# AUDIO2.net
KiCad netlist of a schematic drawn in Altium Designer
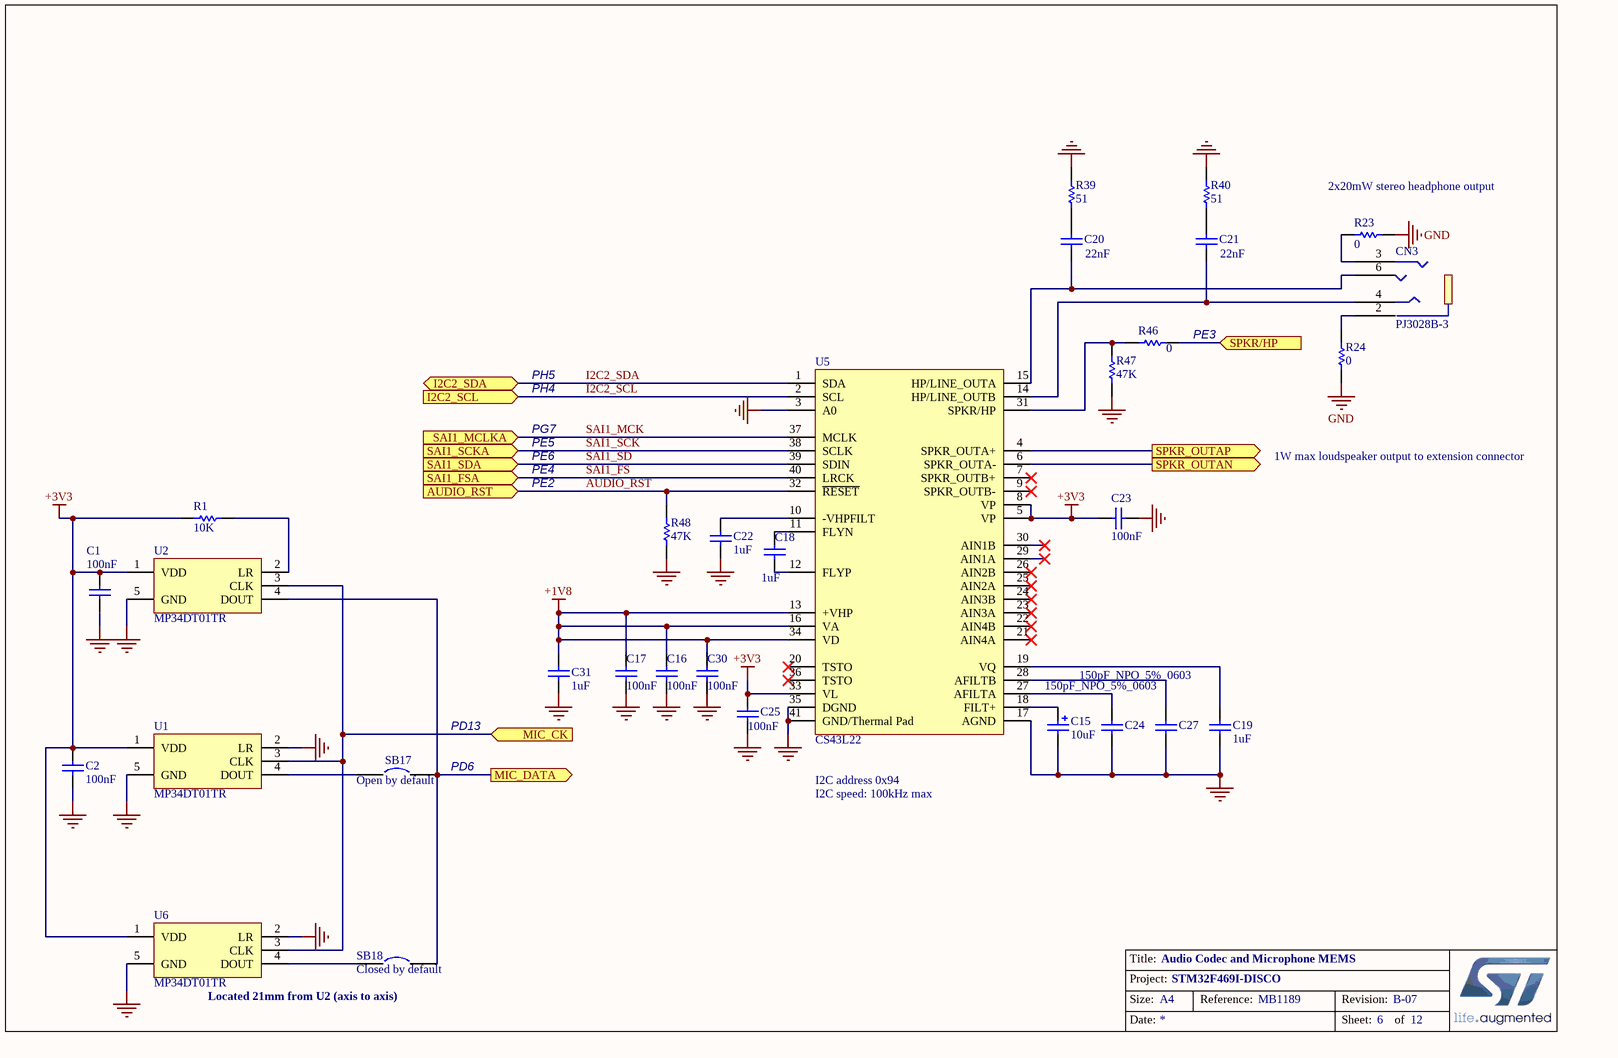
[diagram p0: AUDIO2.SchDoc]

(export (version "E")
  (design (tool "Eeschema 10.0.6"))
  (components
    (comp (ref "C1")
      (value "100nF")
      (footprint "0402C")
      (description "Capacitor")
      (fields (field (name "PUBLISHER") "Altium Limited"))
      (libsource (lib "Miscellaneous Devices") (part "Cap"))
    )
    (comp (ref "C2")
      (value "100nF")
      (footprint "0402C")
      (description "Capacitor")
      (fields (field (name "PUBLISHER") "Altium Limited"))
      (libsource (lib "Miscellaneous Devices") (part "Cap"))
    )
    (comp (ref "C15")
      (value "10uF")
      (footprint "TAN-A")
      (description "Polarized Capacitor (Radial)")
      (fields (field (name "PUBLISHER") "Altium Limited"))
      (libsource (lib "Miscellaneous Devices") (part "Cap Pol1"))
    )
    (comp (ref "C16")
      (value "100nF")
      (footprint "0402C")
      (description "Capacitor")
      (fields (field (name "PUBLISHER") "Altium Limited"))
      (libsource (lib "Miscellaneous Devices") (part "CAP"))
    )
    (comp (ref "C17")
      (value "100nF")
      (footprint "0402C")
      (description "Capacitor")
      (fields (field (name "PUBLISHER") "Altium Limited"))
      (libsource (lib "Miscellaneous Devices") (part "CAP"))
    )
    (comp (ref "C18")
      (value "1uF")
      (footprint "0603C")
      (description "Capacitor")
      (fields (field (name "PUBLISHER") "Altium Limited"))
      (libsource (lib "Miscellaneous Devices") (part "CAP"))
    )
    (comp (ref "C19")
      (value "1uF")
      (footprint "0603C")
      (description "Capacitor")
      (fields (field (name "PUBLISHER") "Altium Limited"))
      (libsource (lib "Miscellaneous Devices") (part "CAP"))
    )
    (comp (ref "C20")
      (value "22nF")
      (footprint "0603C")
      (description "Capacitor,22nF,50V,X7R,10%,0603,YAGEO")
      (libsource (lib "MCD_TOOLS") (part "Cap_22nF_X7R_10%_0603"))
    )
    (comp (ref "C21")
      (value "22nF")
      (footprint "0603C")
      (description "Capacitor,22nF,50V,X7R,10%,0603,YAGEO")
      (libsource (lib "MCD_TOOLS") (part "Cap_22nF_X7R_10%_0603"))
    )
    (comp (ref "C22")
      (value "1uF")
      (footprint "0603C")
      (description "Capacitor")
      (fields (field (name "PUBLISHER") "Altium Limited"))
      (libsource (lib "Miscellaneous Devices") (part "CAP"))
    )
    (comp (ref "C23")
      (value "100nF")
      (footprint "0402C")
      (description "Capacitor")
      (fields (field (name "PUBLISHER") "Altium Limited"))
      (libsource (lib "Miscellaneous Devices") (part "CAP"))
    )
    (comp (ref "C24")
      (value "150pF_NPO_5%_0603")
      (footprint "0603C")
      (description "Capacitor,150pF,50V,NPO,5%,0603,YAGEO")
      (libsource (lib "MCD_TOOLS") (part "Cap_150pF_NPO_5%_0603"))
    )
    (comp (ref "C25")
      (value "100nF")
      (footprint "0402C")
      (description "Capacitor")
      (fields (field (name "PUBLISHER") "Altium Limited"))
      (libsource (lib "Miscellaneous Devices") (part "CAP"))
    )
    (comp (ref "C27")
      (value "150pF_NPO_5%_0603")
      (footprint "0603C")
      (description "Capacitor,150pF,50V,NPO,5%,0603,YAGEO")
      (libsource (lib "MCD_TOOLS") (part "Cap_150pF_NPO_5%_0603"))
    )
    (comp (ref "C30")
      (value "100nF")
      (footprint "0402C")
      (description "Capacitor")
      (fields (field (name "PUBLISHER") "Altium Limited"))
      (libsource (lib "Miscellaneous Devices") (part "CAP"))
    )
    (comp (ref "C31")
      (value "1uF")
      (footprint "0603C")
      (description "Capacitor")
      (fields (field (name "PUBLISHER") "Altium Limited"))
      (libsource (lib "Miscellaneous Devices") (part "CAP"))
    )
    (comp (ref "CN3") (value "PJ3028B-3") (footprint "PJ3028B") (libsource (lib "MB786") (part "PJ3028B-3")))
    (comp (ref "R1")
      (value "10K")
      (footprint "0603R")
      (description "Resistor,0,0402,5%,YAGEO")
      (libsource (lib "MCD_TOOLS") (part "Res_0_5%_0402"))
    )
    (comp (ref "R23")
      (value "0")
      (footprint "0603R")
      (description "Resistor")
      (fields (field (name "PUBLISHER") "Altium Limited"))
      (libsource (lib "") (part "Res1_1"))
    )
    (comp (ref "R24")
      (value "0")
      (footprint "0603R")
      (description "Resistor")
      (fields (field (name "PUBLISHER") "Altium Limited"))
      (libsource (lib "") (part "Res1_1"))
    )
    (comp (ref "R39")
      (value "51")
      (footprint "0402R")
      (description "Resistor,51,0402,1%,YAGEO")
      (libsource (lib "MCD_TOOLS") (part "Res_51_1%_0402"))
    )
    (comp (ref "R40")
      (value "51")
      (footprint "0402R")
      (description "Resistor,51,0402,1%,YAGEO")
      (libsource (lib "MCD_TOOLS") (part "Res_51_1%_0402"))
    )
    (comp (ref "R46")
      (value "0")
      (footprint "0603R")
      (description "Resistor")
      (fields (field (name "PUBLISHER") "Altium Limited"))
      (libsource (lib "Miscellaneous Devices") (part "Res1"))
    )
    (comp (ref "R47")
      (value "47K")
      (footprint "0603R")
      (description "Resistor")
      (fields (field (name "PUBLISHER") "Altium Limited"))
      (libsource (lib "Miscellaneous Devices") (part "Res1"))
    )
    (comp (ref "R48")
      (value "47K")
      (footprint "0603R")
      (description "Resistor")
      (fields (field (name "PUBLISHER") "Altium Limited"))
      (libsource (lib "Miscellaneous Devices") (part "Res1"))
    )
    (comp (ref "SB17")
      (value "Open by default")
      (footprint "SB_0603")
      (description "Circuit Breaker")
      (fields (field (name "PUBLISHER") "Altium Limited"))
      (libsource (lib "Miscellaneous Devices") (part "Circuit Breaker"))
    )
    (comp (ref "SB18")
      (value "Closed by default")
      (footprint "SB_0603")
      (description "Circuit Breaker")
      (fields (field (name "PUBLISHER") "Altium Limited"))
      (libsource (lib "Miscellaneous Devices") (part "Circuit Breaker"))
    )
    (comp (ref "U1")
      (value "MP34DT01TR")
      (footprint "MP34DT01TR")
      (description "MEMS audio sensor")
      (fields (field (name "PUBLISHER") "Altium Limited"))
      (libsource (lib "Almos") (part "MP34DT01TR"))
    )
    (comp (ref "U2")
      (value "MP34DT01TR")
      (footprint "MP34DT01TR")
      (description "MEMS audio sensor")
      (fields (field (name "PUBLISHER") "Altium Limited"))
      (libsource (lib "Almos") (part "MP34DT01TR"))
    )
    (comp (ref "U5")
      (value "CS43L22")
      (footprint "QFN40_0R5_6X6")
      (description "Low Power, Stereo DAC w/Headphone & Speaker Amps")
      (libsource (lib "MCD_TOOLS") (part "CS43L22"))
    )
    (comp (ref "U6")
      (value "MP34DT01TR")
      (footprint "MP34DT01TR")
      (description "MEMS audio sensor")
      (fields (field (name "PUBLISHER") "Altium Limited"))
      (libsource (lib "Almos") (part "MP34DT01TR"))
    )
  )
  (nets
    (net (code "1") (name "+1V8") (class "Default")
      (node (ref "C16") (pin "1") (pinfunction "1_1") (pintype "passive"))
      (node (ref "C17") (pin "1") (pinfunction "1_1") (pintype "passive"))
      (node (ref "C30") (pin "1") (pinfunction "1_1") (pintype "passive"))
      (node (ref "C31") (pin "1") (pinfunction "1_1") (pintype "passive"))
      (node (ref "U5") (pin "13") (pinfunction "+VHP_13") (pintype "passive"))
      (node (ref "U5") (pin "16") (pinfunction "VA_16") (pintype "passive"))
      (node (ref "U5") (pin "34") (pinfunction "VD_34") (pintype "passive"))
    )
    (net (code "2") (name "+3V3") (class "Default")
      (node (ref "C1") (pin "2") (pinfunction "2_2") (pintype "passive"))
      (node (ref "C2") (pin "2") (pinfunction "2_2") (pintype "passive"))
      (node (ref "C23") (pin "2") (pinfunction "2_2") (pintype "passive"))
      (node (ref "C25") (pin "1") (pinfunction "1_1") (pintype "passive"))
      (node (ref "R1") (pin "2") (pinfunction "2_2") (pintype "passive"))
      (node (ref "U1") (pin "1") (pinfunction "VDD_1") (pintype "passive"))
      (node (ref "U2") (pin "1") (pinfunction "VDD_1") (pintype "passive"))
      (node (ref "U5") (pin "33") (pinfunction "VL_33") (pintype "passive"))
      (node (ref "U5") (pin "5") (pinfunction "VP_5") (pintype "passive"))
      (node (ref "U5") (pin "8") (pinfunction "VP_8") (pintype "passive"))
      (node (ref "U6") (pin "1") (pinfunction "VDD_1") (pintype "passive"))
    )
    (net (code "3") (name "/AUDIO_RST") (class "Default")
      (node (ref "R48") (pin "2") (pinfunction "2_2") (pintype "passive"))
      (node (ref "U5") (pin "32") (pinfunction "~{RESET}_32") (pintype "passive"))
    )
    (net (code "4") (name "/I2C2_SCL") (class "Default")
      (node (ref "U5") (pin "2") (pinfunction "SCL_2") (pintype "passive"))
    )
    (net (code "5") (name "/I2C2_SDA") (class "Default")
      (node (ref "U5") (pin "1") (pinfunction "SDA_1") (pintype "passive"))
    )
    (net (code "6") (name "/MIC_CK") (class "Default")
      (node (ref "U1") (pin "3") (pinfunction "CLK_3") (pintype "passive"))
      (node (ref "U2") (pin "3") (pinfunction "CLK_3") (pintype "passive"))
      (node (ref "U6") (pin "3") (pinfunction "CLK_3") (pintype "passive"))
    )
    (net (code "7") (name "/MIC_DATA") (class "Default")
      (node (ref "SB17") (pin "2") (pinfunction "2_2") (pintype "passive"))
      (node (ref "SB18") (pin "2") (pinfunction "2_2") (pintype "passive"))
      (node (ref "U2") (pin "4") (pinfunction "DOUT_4") (pintype "passive"))
    )
    (net (code "8") (name "/SAI1_FS") (class "Default")
      (node (ref "U5") (pin "40") (pinfunction "LRCK_40") (pintype "passive"))
    )
    (net (code "9") (name "/SAI1_MCK") (class "Default")
      (node (ref "U5") (pin "37") (pinfunction "MCLK_37") (pintype "passive"))
    )
    (net (code "10") (name "/SAI1_SCK") (class "Default")
      (node (ref "U5") (pin "38") (pinfunction "SCLK_38") (pintype "passive"))
    )
    (net (code "11") (name "/SAI1_SD") (class "Default")
      (node (ref "U5") (pin "39") (pinfunction "SDIN_39") (pintype "passive"))
    )
    (net (code "12") (name "/SPKR_OUTAN") (class "Default")
      (node (ref "U5") (pin "6") (pinfunction "SPKR_OUTA-_6") (pintype "passive"))
    )
    (net (code "13") (name "/SPKR_OUTAP") (class "Default")
      (node (ref "U5") (pin "4") (pinfunction "SPKR_OUTA+_4") (pintype "passive"))
    )
    (net (code "14") (name "/SPKR{slash}HP") (class "Default")
      (node (ref "R46") (pin "2") (pinfunction "2_2") (pintype "passive"))
    )
    (net (code "15") (name "GND") (class "Default")
      (node (ref "C1") (pin "1") (pinfunction "1_1") (pintype "passive"))
      (node (ref "C15") (pin "2") (pinfunction "2_2") (pintype "passive"))
      (node (ref "C16") (pin "2") (pinfunction "2_2") (pintype "passive"))
      (node (ref "C17") (pin "2") (pinfunction "2_2") (pintype "passive"))
      (node (ref "C19") (pin "1") (pinfunction "1_1") (pintype "passive"))
      (node (ref "C2") (pin "1") (pinfunction "1_1") (pintype "passive"))
      (node (ref "C22") (pin "1") (pinfunction "1_1") (pintype "passive"))
      (node (ref "C23") (pin "1") (pinfunction "1_1") (pintype "passive"))
      (node (ref "C24") (pin "1") (pinfunction "1_1") (pintype "passive"))
      (node (ref "C25") (pin "2") (pinfunction "2_2") (pintype "passive"))
      (node (ref "C27") (pin "1") (pinfunction "1_1") (pintype "passive"))
      (node (ref "C30") (pin "2") (pinfunction "2_2") (pintype "passive"))
      (node (ref "C31") (pin "2") (pinfunction "2_2") (pintype "passive"))
      (node (ref "R23") (pin "2") (pinfunction "2_2") (pintype "passive"))
      (node (ref "R24") (pin "2") (pinfunction "2_2") (pintype "passive"))
      (node (ref "R39") (pin "2") (pinfunction "2_2") (pintype "passive"))
      (node (ref "R40") (pin "2") (pinfunction "2_2") (pintype "passive"))
      (node (ref "R47") (pin "2") (pinfunction "2_2") (pintype "passive"))
      (node (ref "R48") (pin "1") (pinfunction "1_1") (pintype "passive"))
      (node (ref "U1") (pin "2") (pinfunction "LR_2") (pintype "passive"))
      (node (ref "U1") (pin "5") (pinfunction "GND_5") (pintype "passive"))
      (node (ref "U2") (pin "5") (pinfunction "GND_5") (pintype "passive"))
      (node (ref "U5") (pin "17") (pinfunction "AGND_17") (pintype "passive"))
      (node (ref "U5") (pin "3") (pinfunction "A0_3") (pintype "passive"))
      (node (ref "U5") (pin "35") (pinfunction "DGND_35") (pintype "passive"))
      (node (ref "U5") (pin "41") (pinfunction "GND/Thermal_Pad_41") (pintype "passive"))
      (node (ref "U6") (pin "2") (pinfunction "LR_2") (pintype "passive"))
      (node (ref "U6") (pin "5") (pinfunction "GND_5") (pintype "passive"))
    )
    (net (code "16") (name "Net-(C20-Pad2)") (class "Default")
      (node (ref "C20") (pin "2") (pinfunction "2_2") (pintype "passive"))
      (node (ref "R39") (pin "1") (pinfunction "1_1") (pintype "passive"))
    )
    (net (code "17") (name "Net-(C21-Pad2)") (class "Default")
      (node (ref "C21") (pin "2") (pinfunction "2_2") (pintype "passive"))
      (node (ref "R40") (pin "1") (pinfunction "1_1") (pintype "passive"))
    )
    (net (code "18") (name "Net-(CN3-Pad2)") (class "Default")
      (node (ref "CN3") (pin "2") (pintype "passive"))
      (node (ref "R24") (pin "1") (pinfunction "1_1") (pintype "passive"))
    )
    (net (code "19") (name "Net-(CN3-Pad3)") (class "Default")
      (node (ref "CN3") (pin "3") (pintype "passive"))
      (node (ref "R23") (pin "1") (pinfunction "1_1") (pintype "passive"))
    )
    (net (code "20") (name "Net-(U1-DOUT)") (class "Default")
      (node (ref "SB17") (pin "1") (pinfunction "1_1") (pintype "passive"))
      (node (ref "U1") (pin "4") (pinfunction "DOUT_4") (pintype "passive"))
    )
    (net (code "21") (name "Net-(U2-LR)") (class "Default")
      (node (ref "R1") (pin "1") (pinfunction "1_1") (pintype "passive"))
      (node (ref "U2") (pin "2") (pinfunction "LR_2") (pintype "passive"))
    )
    (net (code "22") (name "Net-(U5--VHPFILT)") (class "Default")
      (node (ref "C22") (pin "2") (pinfunction "2_2") (pintype "passive"))
      (node (ref "U5") (pin "10") (pinfunction "-VHPFILT_10") (pintype "passive"))
    )
    (net (code "23") (name "Net-(U5-AFILTA)") (class "Default")
      (node (ref "C24") (pin "2") (pinfunction "2_2") (pintype "passive"))
      (node (ref "U5") (pin "27") (pinfunction "AFILTA_27") (pintype "passive"))
    )
    (net (code "24") (name "Net-(U5-AFILTB)") (class "Default")
      (node (ref "C27") (pin "2") (pinfunction "2_2") (pintype "passive"))
      (node (ref "U5") (pin "28") (pinfunction "AFILTB_28") (pintype "passive"))
    )
    (net (code "25") (name "Net-(U5-FILT+)") (class "Default")
      (node (ref "C15") (pin "1") (pinfunction "1_1") (pintype "passive"))
      (node (ref "U5") (pin "18") (pinfunction "FILT+_18") (pintype "passive"))
    )
    (net (code "26") (name "Net-(U5-FLYN)") (class "Default")
      (node (ref "C18") (pin "1") (pinfunction "1_1") (pintype "passive"))
      (node (ref "U5") (pin "11") (pinfunction "FLYN_11") (pintype "passive"))
    )
    (net (code "27") (name "Net-(U5-FLYP)") (class "Default")
      (node (ref "C18") (pin "2") (pinfunction "2_2") (pintype "passive"))
      (node (ref "U5") (pin "12") (pinfunction "FLYP_12") (pintype "passive"))
    )
    (net (code "28") (name "Net-(U5-HP{slash}LINE_OUTA)") (class "Default")
      (node (ref "C20") (pin "1") (pinfunction "1_1") (pintype "passive"))
      (node (ref "CN3") (pin "6") (pintype "passive"))
      (node (ref "U5") (pin "15") (pinfunction "HP/LINE_OUTA_15") (pintype "passive"))
    )
    (net (code "29") (name "Net-(U5-HP{slash}LINE_OUTB)") (class "Default")
      (node (ref "C21") (pin "1") (pinfunction "1_1") (pintype "passive"))
      (node (ref "CN3") (pin "4") (pintype "passive"))
      (node (ref "U5") (pin "14") (pinfunction "HP/LINE_OUTB_14") (pintype "passive"))
    )
    (net (code "30") (name "Net-(U5-SPKR{slash}HP)") (class "Default")
      (node (ref "R46") (pin "1") (pinfunction "1_1") (pintype "passive"))
      (node (ref "R47") (pin "1") (pinfunction "1_1") (pintype "passive"))
      (node (ref "U5") (pin "31") (pinfunction "SPKR/HP_31") (pintype "passive"))
    )
    (net (code "31") (name "Net-(U5-VQ)") (class "Default")
      (node (ref "C19") (pin "2") (pinfunction "2_2") (pintype "passive"))
      (node (ref "U5") (pin "19") (pinfunction "VQ_19") (pintype "passive"))
    )
    (net (code "32") (name "Net-(U6-DOUT)") (class "Default")
      (node (ref "SB18") (pin "1") (pinfunction "1_1") (pintype "passive"))
      (node (ref "U6") (pin "4") (pinfunction "DOUT_4") (pintype "passive"))
    )
    (net (code "33") (name "unconnected-(U5-AIN1A-Pad29)") (class "Default")
      (node (ref "U5") (pin "29") (pinfunction "AIN1A_29") (pintype "passive+no_connect"))
    )
    (net (code "34") (name "unconnected-(U5-AIN1B-Pad30)") (class "Default")
      (node (ref "U5") (pin "30") (pinfunction "AIN1B_30") (pintype "passive+no_connect"))
    )
    (net (code "35") (name "unconnected-(U5-AIN2A-Pad25)") (class "Default")
      (node (ref "U5") (pin "25") (pinfunction "AIN2A_25") (pintype "passive+no_connect"))
    )
    (net (code "36") (name "unconnected-(U5-AIN2B-Pad26)") (class "Default")
      (node (ref "U5") (pin "26") (pinfunction "AIN2B_26") (pintype "passive+no_connect"))
    )
    (net (code "37") (name "unconnected-(U5-AIN3A-Pad23)") (class "Default")
      (node (ref "U5") (pin "23") (pinfunction "AIN3A_23") (pintype "passive+no_connect"))
    )
    (net (code "38") (name "unconnected-(U5-AIN3B-Pad24)") (class "Default")
      (node (ref "U5") (pin "24") (pinfunction "AIN3B_24") (pintype "passive+no_connect"))
    )
    (net (code "39") (name "unconnected-(U5-AIN4A-Pad21)") (class "Default")
      (node (ref "U5") (pin "21") (pinfunction "AIN4A_21") (pintype "passive+no_connect"))
    )
    (net (code "40") (name "unconnected-(U5-AIN4B-Pad22)") (class "Default")
      (node (ref "U5") (pin "22") (pinfunction "AIN4B_22") (pintype "passive+no_connect"))
    )
    (net (code "41") (name "unconnected-(U5-SPKR_OUTB+-Pad7)") (class "Default")
      (node (ref "U5") (pin "7") (pinfunction "SPKR_OUTB+_7") (pintype "passive+no_connect"))
    )
    (net (code "42") (name "unconnected-(U5-SPKR_OUTB--Pad9)") (class "Default")
      (node (ref "U5") (pin "9") (pinfunction "SPKR_OUTB-_9") (pintype "passive+no_connect"))
    )
    (net (code "43") (name "unconnected-(U5-TSTO-Pad20)") (class "Default")
      (node (ref "U5") (pin "20") (pinfunction "TSTO_20") (pintype "passive+no_connect"))
    )
    (net (code "44") (name "unconnected-(U5-TSTO-Pad36)") (class "Default")
      (node (ref "U5") (pin "36") (pinfunction "TSTO_36") (pintype "passive+no_connect"))
    )
  )
)
